# PassiveFilter.net
KiCad netlist of a schematic drawn in Altium Designer
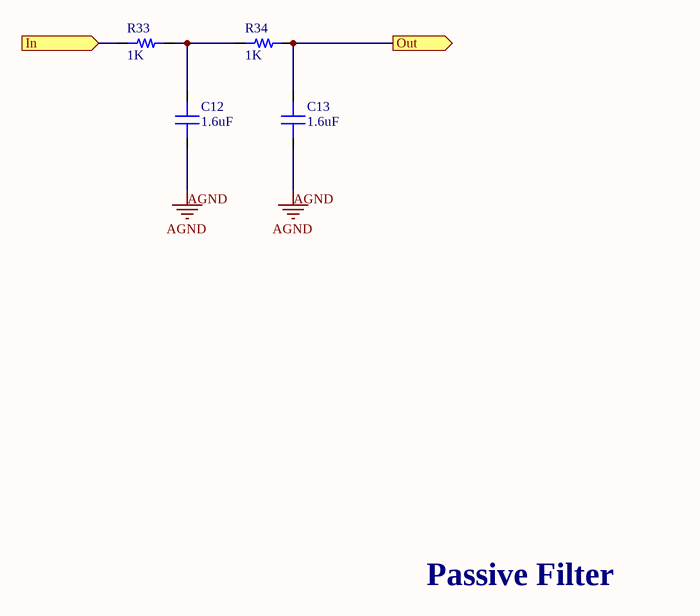
[diagram p0: PassiveFilter.SchDoc]

(export (version "E")
  (design (tool "Eeschema 10.0.6"))
  (components
    (comp (ref "C12")
      (value "capacitor")
      (footprint "0603")
      (description "Generic 0603 capacitor")
      (fields (field (name "CAPACITANCE") "1.6uF") (field (name "VOLTAGE") "50"))
      (libsource (lib "altlib") (part "capacitor"))
    )
    (comp (ref "C13")
      (value "capacitor")
      (footprint "0603")
      (description "Generic 0603 capacitor")
      (fields (field (name "CAPACITANCE") "1.6uF") (field (name "VOLTAGE") "50"))
      (libsource (lib "altlib") (part "capacitor"))
    )
    (comp (ref "R33")
      (value "resistor")
      (footprint "0603")
      (fields (field (name "RESISTANCE") "1K"))
      (libsource (lib "altlib") (part "resistor"))
    )
    (comp (ref "R34")
      (value "resistor")
      (footprint "0603")
      (fields (field (name "RESISTANCE") "1K"))
      (libsource (lib "altlib") (part "resistor"))
    )
  )
  (nets
    (net (code "1") (name "/In") (class "Default")
      (node (ref "R33") (pin "1") (pinfunction "1_1") (pintype "passive"))
    )
    (net (code "2") (name "/Out") (class "Default")
      (node (ref "C13") (pin "2") (pinfunction "2_2") (pintype "passive"))
      (node (ref "R34") (pin "2") (pinfunction "2_2") (pintype "passive"))
    )
    (net (code "3") (name "AGND") (class "Default")
      (node (ref "C12") (pin "1") (pinfunction "1_1") (pintype "passive"))
      (node (ref "C13") (pin "1") (pinfunction "1_1") (pintype "passive"))
    )
    (net (code "4") (name "Net-(C12-Pad2)") (class "Default")
      (node (ref "C12") (pin "2") (pinfunction "2_2") (pintype "passive"))
      (node (ref "R33") (pin "2") (pinfunction "2_2") (pintype "passive"))
      (node (ref "R34") (pin "1") (pinfunction "1_1") (pintype "passive"))
    )
  )
)
